# cannonLed.net
KiCad netlist of a schematic drawn in Altium Designer
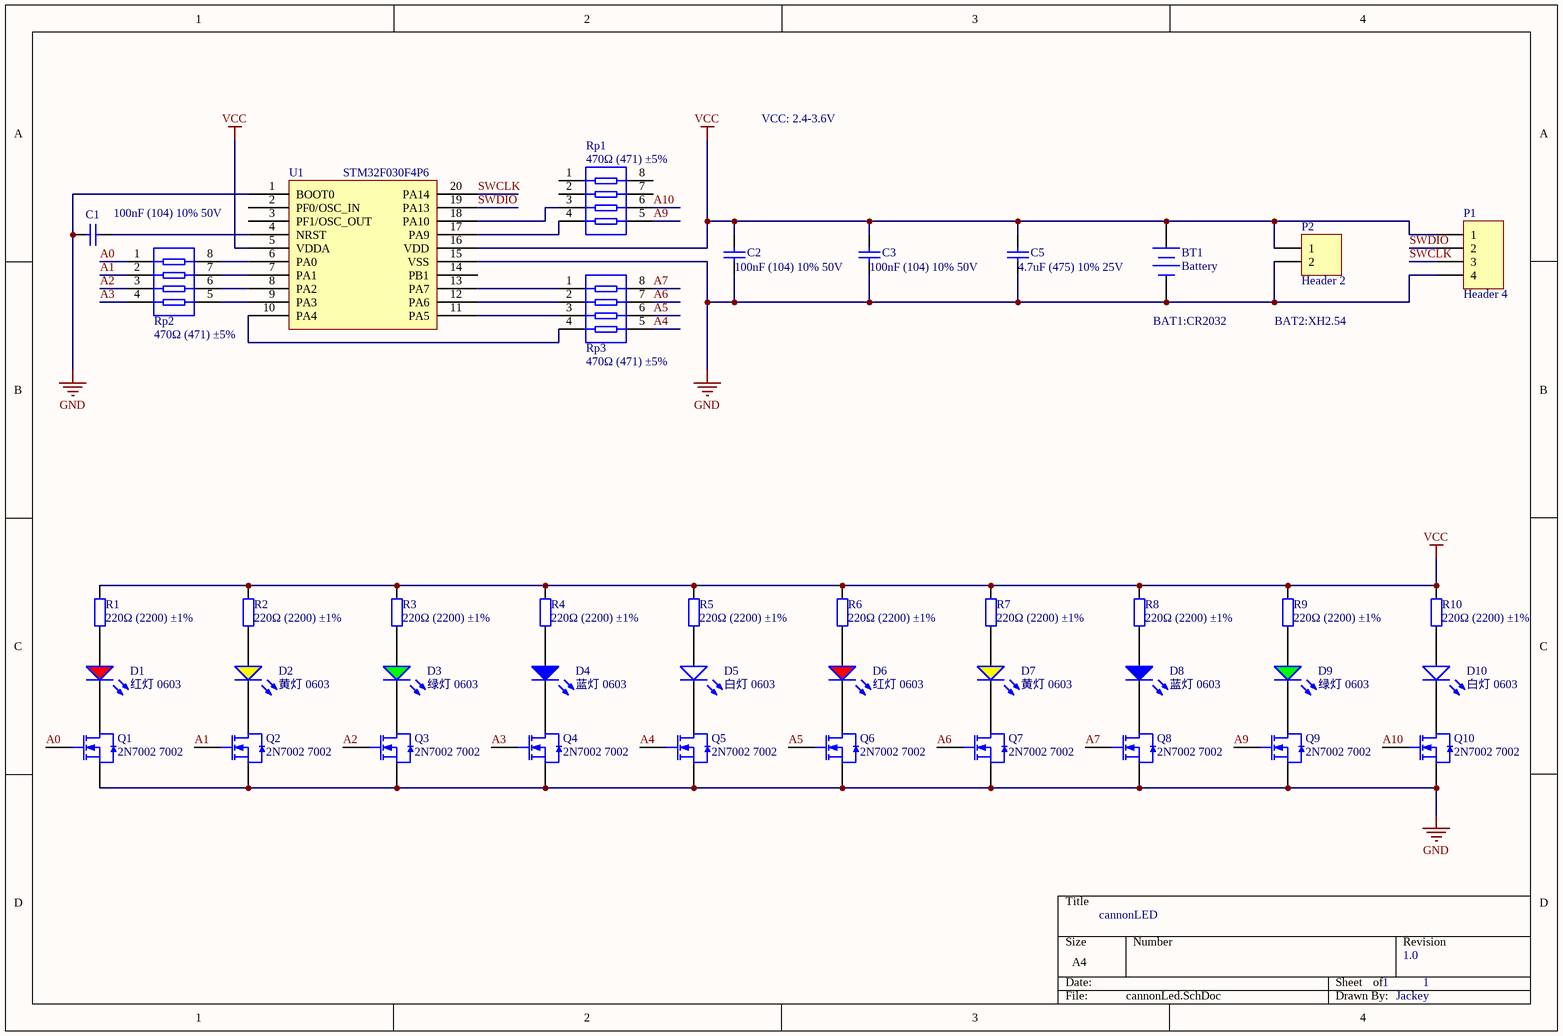
[diagram p0: cannonLed.SchDoc]

(export (version "E")
  (design (tool "Eeschema 10.0.6"))
  (components
    (comp (ref "BT1")
      (value "Battery")
      (footprint "CR2032")
      (description "Multicell Battery")
      (fields (field (name "PUBLISHER") "Altium Limited"))
      (libsource (lib "Miscellaneous Devices") (part "Battery"))
    )
    (comp (ref "C1")
      (value "100nF (104) 10% 50V")
      (footprint "0603_C")
      (description "贴片电容")
      (libsource (lib "Cap") (part "0603 100nF (104) 10% 50V"))
    )
    (comp (ref "C2")
      (value "100nF (104) 10% 50V")
      (footprint "0603_C")
      (description "贴片电容")
      (libsource (lib "Cap") (part "0603 100nF (104) 10% 50V"))
    )
    (comp (ref "C3")
      (value "100nF (104) 10% 50V")
      (footprint "0603_C")
      (description "贴片电容")
      (libsource (lib "Cap") (part "0603 100nF (104) 10% 50V"))
    )
    (comp (ref "C5")
      (value "4.7uF (475) 10% 25V")
      (footprint "0805_C")
      (description "贴片电容")
      (libsource (lib "Cap") (part "0805 4.7uF (475) 10% 25V"))
    )
    (comp (ref "D1")
      (value "红灯 0603")
      (footprint "0603_LED_S1")
      (description "发光二极管")
      (libsource (lib "LED") (part "0603 红灯"))
    )
    (comp (ref "D2")
      (value "黄灯 0603")
      (footprint "0603_LED_S1")
      (description "发光二极管")
      (libsource (lib "LED") (part "0603 黄灯"))
    )
    (comp (ref "D3")
      (value "绿灯 0603")
      (footprint "0603_LED_S1")
      (description "发光二极管")
      (libsource (lib "LED") (part "0603 绿灯"))
    )
    (comp (ref "D4")
      (value "蓝灯 0603")
      (footprint "0603_LED_S1")
      (description "发光二极管")
      (libsource (lib "LED") (part "0603 蓝灯"))
    )
    (comp (ref "D5")
      (value "白灯 0603")
      (footprint "0603_LED_S1")
      (description "发光二极管")
      (libsource (lib "LED") (part "0603 白灯"))
    )
    (comp (ref "D6")
      (value "红灯 0603")
      (footprint "0603_LED_S1")
      (description "发光二极管")
      (libsource (lib "LED") (part "0603 红灯"))
    )
    (comp (ref "D7")
      (value "黄灯 0603")
      (footprint "0603_LED_S1")
      (description "发光二极管")
      (libsource (lib "LED") (part "0603 黄灯"))
    )
    (comp (ref "D8")
      (value "蓝灯 0603")
      (footprint "0603_LED_S1")
      (description "发光二极管")
      (libsource (lib "LED") (part "0603 蓝灯"))
    )
    (comp (ref "D9")
      (value "绿灯 0603")
      (footprint "0603_LED_S1")
      (description "发光二极管")
      (libsource (lib "LED") (part "0603 绿灯"))
    )
    (comp (ref "D10")
      (value "白灯 0603")
      (footprint "0603_LED_S1")
      (description "发光二极管")
      (libsource (lib "LED") (part "0603 白灯"))
    )
    (comp (ref "P1")
      (value "Header 4")
      (footprint "HDR1X4")
      (description "Header, 4-Pin")
      (fields (field (name "PUBLISHER") "Altium Limited"))
      (libsource (lib "Miscellaneous Connectors") (part "Header 4"))
    )
    (comp (ref "P2")
      (value "Header 2")
      (footprint "HDR1X2")
      (description "Header, 2-Pin")
      (fields (field (name "PUBLISHER") "Altium Limited"))
      (libsource (lib "Miscellaneous Connectors") (part "Header 2"))
    )
    (comp (ref "Q1")
      (value "2N7002 7002")
      (footprint "SOT-23(SOT-23-3)")
      (description "MOS(场效应管)")
      (libsource (lib "MOS") (part "2N7002 7002"))
    )
    (comp (ref "Q2")
      (value "2N7002 7002")
      (footprint "SOT-23(SOT-23-3)")
      (description "MOS(场效应管)")
      (libsource (lib "MOS") (part "2N7002 7002"))
    )
    (comp (ref "Q3")
      (value "2N7002 7002")
      (footprint "SOT-23(SOT-23-3)")
      (description "MOS(场效应管)")
      (libsource (lib "MOS") (part "2N7002 7002"))
    )
    (comp (ref "Q4")
      (value "2N7002 7002")
      (footprint "SOT-23(SOT-23-3)")
      (description "MOS(场效应管)")
      (libsource (lib "MOS") (part "2N7002 7002"))
    )
    (comp (ref "Q5")
      (value "2N7002 7002")
      (footprint "SOT-23(SOT-23-3)")
      (description "MOS(场效应管)")
      (libsource (lib "MOS") (part "2N7002 7002"))
    )
    (comp (ref "Q6")
      (value "2N7002 7002")
      (footprint "SOT-23(SOT-23-3)")
      (description "MOS(场效应管)")
      (libsource (lib "MOS") (part "2N7002 7002"))
    )
    (comp (ref "Q7")
      (value "2N7002 7002")
      (footprint "SOT-23(SOT-23-3)")
      (description "MOS(场效应管)")
      (libsource (lib "MOS") (part "2N7002 7002"))
    )
    (comp (ref "Q8")
      (value "2N7002 7002")
      (footprint "SOT-23(SOT-23-3)")
      (description "MOS(场效应管)")
      (libsource (lib "MOS") (part "2N7002 7002"))
    )
    (comp (ref "Q9")
      (value "2N7002 7002")
      (footprint "SOT-23(SOT-23-3)")
      (description "MOS(场效应管)")
      (libsource (lib "MOS") (part "2N7002 7002"))
    )
    (comp (ref "Q10")
      (value "2N7002 7002")
      (footprint "SOT-23(SOT-23-3)")
      (description "MOS(场效应管)")
      (libsource (lib "MOS") (part "2N7002 7002"))
    )
    (comp (ref "R1")
      (value "220Ω (2200) ±1%")
      (footprint "0603_R")
      (description "贴片电阻")
      (libsource (lib "RES") (part "0603 220Ω (2200) 1%"))
    )
    (comp (ref "R2")
      (value "220Ω (2200) ±1%")
      (footprint "0603_R")
      (description "贴片电阻")
      (libsource (lib "") (part "0603 220Ω (2200) 1%_1"))
    )
    (comp (ref "R3")
      (value "220Ω (2200) ±1%")
      (footprint "0603_R")
      (description "贴片电阻")
      (libsource (lib "") (part "0603 220Ω (2200) 1%_1"))
    )
    (comp (ref "R4")
      (value "220Ω (2200) ±1%")
      (footprint "0603_R")
      (description "贴片电阻")
      (libsource (lib "") (part "0603 220Ω (2200) 1%_1"))
    )
    (comp (ref "R5")
      (value "220Ω (2200) ±1%")
      (footprint "0603_R")
      (description "贴片电阻")
      (libsource (lib "") (part "0603 220Ω (2200) 1%_1"))
    )
    (comp (ref "R6")
      (value "220Ω (2200) ±1%")
      (footprint "0603_R")
      (description "贴片电阻")
      (libsource (lib "") (part "0603 220Ω (2200) 1%_1"))
    )
    (comp (ref "R7")
      (value "220Ω (2200) ±1%")
      (footprint "0603_R")
      (description "贴片电阻")
      (libsource (lib "") (part "0603 220Ω (2200) 1%_1"))
    )
    (comp (ref "R8")
      (value "220Ω (2200) ±1%")
      (footprint "0603_R")
      (description "贴片电阻")
      (libsource (lib "") (part "0603 220Ω (2200) 1%_1"))
    )
    (comp (ref "R9")
      (value "220Ω (2200) ±1%")
      (footprint "0603_R")
      (description "贴片电阻")
      (libsource (lib "") (part "0603 220Ω (2200) 1%_1"))
    )
    (comp (ref "R10")
      (value "220Ω (2200) ±1%")
      (footprint "0603_R")
      (description "贴片电阻")
      (libsource (lib "") (part "0603 220Ω (2200) 1%_1"))
    )
    (comp (ref "Rp1")
      (value "470Ω (471) ±5%")
      (footprint "0603_Rx4")
      (description "贴片排阻")
      (libsource (lib "RES") (part "0603*4 470Ω (471) 5%"))
    )
    (comp (ref "Rp2")
      (value "470Ω (471) ±5%")
      (footprint "0603_Rx4")
      (description "贴片排阻")
      (libsource (lib "RES") (part "0603*4 470Ω (471) 5%"))
    )
    (comp (ref "Rp3")
      (value "470Ω (471) ±5%")
      (footprint "0603_Rx4")
      (description "贴片排阻")
      (libsource (lib "RES") (part "0603*4 470Ω (471) 5%"))
    )
    (comp (ref "U1")
      (value "STM32F030F4P6")
      (footprint "TSSOP-20")
      (description "ARM")
      (libsource (lib "MCU") (part "STM32F030F4P6"))
    )
  )
  (nets
    (net (code "1") (name "/A0") (class "Default")
      (node (ref "Q1") (pin "1") (pinfunction "G_1") (pintype "passive"))
      (node (ref "Rp2") (pin "1") (pinfunction "1_1") (pintype "passive"))
    )
    (net (code "2") (name "/A1") (class "Default")
      (node (ref "Q2") (pin "1") (pinfunction "G_1") (pintype "passive"))
      (node (ref "Rp2") (pin "2") (pinfunction "2_2") (pintype "passive"))
    )
    (net (code "3") (name "/A2") (class "Default")
      (node (ref "Q3") (pin "1") (pinfunction "G_1") (pintype "passive"))
      (node (ref "Rp2") (pin "3") (pinfunction "3_3") (pintype "passive"))
    )
    (net (code "4") (name "/A3") (class "Default")
      (node (ref "Q4") (pin "1") (pinfunction "G_1") (pintype "passive"))
      (node (ref "Rp2") (pin "4") (pinfunction "4_4") (pintype "passive"))
    )
    (net (code "5") (name "/A4") (class "Default")
      (node (ref "Q5") (pin "1") (pinfunction "G_1") (pintype "passive"))
      (node (ref "Rp3") (pin "5") (pinfunction "5_5") (pintype "passive"))
    )
    (net (code "6") (name "/A5") (class "Default")
      (node (ref "Q6") (pin "1") (pinfunction "G_1") (pintype "passive"))
      (node (ref "Rp3") (pin "6") (pinfunction "6_6") (pintype "passive"))
    )
    (net (code "7") (name "/A6") (class "Default")
      (node (ref "Q7") (pin "1") (pinfunction "G_1") (pintype "passive"))
      (node (ref "Rp3") (pin "7") (pinfunction "7_7") (pintype "passive"))
    )
    (net (code "8") (name "/A7") (class "Default")
      (node (ref "Q8") (pin "1") (pinfunction "G_1") (pintype "passive"))
      (node (ref "Rp3") (pin "8") (pinfunction "8_8") (pintype "passive"))
    )
    (net (code "9") (name "/A9") (class "Default")
      (node (ref "Q9") (pin "1") (pinfunction "G_1") (pintype "passive"))
      (node (ref "Rp1") (pin "5") (pinfunction "5_5") (pintype "passive"))
    )
    (net (code "10") (name "/A10") (class "Default")
      (node (ref "Q10") (pin "1") (pinfunction "G_1") (pintype "passive"))
      (node (ref "Rp1") (pin "6") (pinfunction "6_6") (pintype "passive"))
    )
    (net (code "11") (name "/SWCLK") (class "Default")
      (node (ref "P1") (pin "3") (pinfunction "3_3") (pintype "passive"))
      (node (ref "U1") (pin "20") (pinfunction "PA14_20") (pintype "passive"))
    )
    (net (code "12") (name "/SWDIO") (class "Default")
      (node (ref "P1") (pin "2") (pinfunction "2_2") (pintype "passive"))
      (node (ref "U1") (pin "19") (pinfunction "PA13_19") (pintype "passive"))
    )
    (net (code "13") (name "GND") (class "Default")
      (node (ref "BT1") (pin "2") (pinfunction "-_2") (pintype "passive"))
      (node (ref "C1") (pin "1") (pinfunction "1_1") (pintype "passive"))
      (node (ref "C2") (pin "1") (pinfunction "1_1") (pintype "passive"))
      (node (ref "C3") (pin "1") (pinfunction "1_1") (pintype "passive"))
      (node (ref "C5") (pin "1") (pinfunction "1_1") (pintype "passive"))
      (node (ref "P1") (pin "4") (pinfunction "4_4") (pintype "passive"))
      (node (ref "P2") (pin "2") (pinfunction "2_2") (pintype "passive"))
      (node (ref "Q1") (pin "2") (pinfunction "S_2") (pintype "passive"))
      (node (ref "Q10") (pin "2") (pinfunction "S_2") (pintype "passive"))
      (node (ref "Q2") (pin "2") (pinfunction "S_2") (pintype "passive"))
      (node (ref "Q3") (pin "2") (pinfunction "S_2") (pintype "passive"))
      (node (ref "Q4") (pin "2") (pinfunction "S_2") (pintype "passive"))
      (node (ref "Q5") (pin "2") (pinfunction "S_2") (pintype "passive"))
      (node (ref "Q6") (pin "2") (pinfunction "S_2") (pintype "passive"))
      (node (ref "Q7") (pin "2") (pinfunction "S_2") (pintype "passive"))
      (node (ref "Q8") (pin "2") (pinfunction "S_2") (pintype "passive"))
      (node (ref "Q9") (pin "2") (pinfunction "S_2") (pintype "passive"))
      (node (ref "U1") (pin "1") (pinfunction "BOOT0_1") (pintype "passive"))
      (node (ref "U1") (pin "15") (pinfunction "VSS_15") (pintype "passive"))
    )
    (net (code "14") (name "Net-(D1-PadA)") (class "Default")
      (node (ref "D1") (pin "A") (pinfunction "A_A") (pintype "passive"))
      (node (ref "R1") (pin "1") (pinfunction "1_1") (pintype "passive"))
    )
    (net (code "15") (name "Net-(D2-PadA)") (class "Default")
      (node (ref "D2") (pin "A") (pinfunction "A_A") (pintype "passive"))
      (node (ref "R2") (pin "2") (pinfunction "2_2") (pintype "passive"))
    )
    (net (code "16") (name "Net-(D3-PadA)") (class "Default")
      (node (ref "D3") (pin "A") (pinfunction "A_A") (pintype "passive"))
      (node (ref "R3") (pin "2") (pinfunction "2_2") (pintype "passive"))
    )
    (net (code "17") (name "Net-(D4-PadA)") (class "Default")
      (node (ref "D4") (pin "A") (pinfunction "A_A") (pintype "passive"))
      (node (ref "R4") (pin "2") (pinfunction "2_2") (pintype "passive"))
    )
    (net (code "18") (name "Net-(D5-PadA)") (class "Default")
      (node (ref "D5") (pin "A") (pinfunction "A_A") (pintype "passive"))
      (node (ref "R5") (pin "2") (pinfunction "2_2") (pintype "passive"))
    )
    (net (code "19") (name "Net-(D6-PadA)") (class "Default")
      (node (ref "D6") (pin "A") (pinfunction "A_A") (pintype "passive"))
      (node (ref "R6") (pin "2") (pinfunction "2_2") (pintype "passive"))
    )
    (net (code "20") (name "Net-(D7-PadA)") (class "Default")
      (node (ref "D7") (pin "A") (pinfunction "A_A") (pintype "passive"))
      (node (ref "R7") (pin "2") (pinfunction "2_2") (pintype "passive"))
    )
    (net (code "21") (name "Net-(D8-PadA)") (class "Default")
      (node (ref "D8") (pin "A") (pinfunction "A_A") (pintype "passive"))
      (node (ref "R8") (pin "2") (pinfunction "2_2") (pintype "passive"))
    )
    (net (code "22") (name "Net-(D9-PadA)") (class "Default")
      (node (ref "D9") (pin "A") (pinfunction "A_A") (pintype "passive"))
      (node (ref "R9") (pin "2") (pinfunction "2_2") (pintype "passive"))
    )
    (net (code "23") (name "Net-(D10-PadA)") (class "Default")
      (node (ref "D10") (pin "A") (pinfunction "A_A") (pintype "passive"))
      (node (ref "R10") (pin "2") (pinfunction "2_2") (pintype "passive"))
    )
    (net (code "24") (name "Net-(Q1-D)") (class "Default")
      (node (ref "D1") (pin "K") (pinfunction "K_K") (pintype "passive"))
      (node (ref "Q1") (pin "3") (pinfunction "D_3") (pintype "passive"))
    )
    (net (code "25") (name "Net-(Q2-D)") (class "Default")
      (node (ref "D2") (pin "K") (pinfunction "K_K") (pintype "passive"))
      (node (ref "Q2") (pin "3") (pinfunction "D_3") (pintype "passive"))
    )
    (net (code "26") (name "Net-(Q3-D)") (class "Default")
      (node (ref "D3") (pin "K") (pinfunction "K_K") (pintype "passive"))
      (node (ref "Q3") (pin "3") (pinfunction "D_3") (pintype "passive"))
    )
    (net (code "27") (name "Net-(Q4-D)") (class "Default")
      (node (ref "D4") (pin "K") (pinfunction "K_K") (pintype "passive"))
      (node (ref "Q4") (pin "3") (pinfunction "D_3") (pintype "passive"))
    )
    (net (code "28") (name "Net-(Q5-D)") (class "Default")
      (node (ref "D5") (pin "K") (pinfunction "K_K") (pintype "passive"))
      (node (ref "Q5") (pin "3") (pinfunction "D_3") (pintype "passive"))
    )
    (net (code "29") (name "Net-(Q6-D)") (class "Default")
      (node (ref "D6") (pin "K") (pinfunction "K_K") (pintype "passive"))
      (node (ref "Q6") (pin "3") (pinfunction "D_3") (pintype "passive"))
    )
    (net (code "30") (name "Net-(Q7-D)") (class "Default")
      (node (ref "D7") (pin "K") (pinfunction "K_K") (pintype "passive"))
      (node (ref "Q7") (pin "3") (pinfunction "D_3") (pintype "passive"))
    )
    (net (code "31") (name "Net-(Q8-D)") (class "Default")
      (node (ref "D8") (pin "K") (pinfunction "K_K") (pintype "passive"))
      (node (ref "Q8") (pin "3") (pinfunction "D_3") (pintype "passive"))
    )
    (net (code "32") (name "Net-(Q9-D)") (class "Default")
      (node (ref "D9") (pin "K") (pinfunction "K_K") (pintype "passive"))
      (node (ref "Q9") (pin "3") (pinfunction "D_3") (pintype "passive"))
    )
    (net (code "33") (name "Net-(Q10-D)") (class "Default")
      (node (ref "D10") (pin "K") (pinfunction "K_K") (pintype "passive"))
      (node (ref "Q10") (pin "3") (pinfunction "D_3") (pintype "passive"))
    )
    (net (code "34") (name "Net-(U1-NRST)") (class "Default")
      (node (ref "C1") (pin "2") (pinfunction "2_2") (pintype "passive"))
      (node (ref "U1") (pin "4") (pinfunction "NRST_4") (pintype "passive"))
    )
    (net (code "35") (name "Net-(U1-PA0)") (class "Default")
      (node (ref "Rp2") (pin "8") (pinfunction "8_8") (pintype "passive"))
      (node (ref "U1") (pin "6") (pinfunction "PA0_6") (pintype "passive"))
    )
    (net (code "36") (name "Net-(U1-PA1)") (class "Default")
      (node (ref "Rp2") (pin "7") (pinfunction "7_7") (pintype "passive"))
      (node (ref "U1") (pin "7") (pinfunction "PA1_7") (pintype "passive"))
    )
    (net (code "37") (name "Net-(U1-PA2)") (class "Default")
      (node (ref "Rp2") (pin "6") (pinfunction "6_6") (pintype "passive"))
      (node (ref "U1") (pin "8") (pinfunction "PA2_8") (pintype "passive"))
    )
    (net (code "38") (name "Net-(U1-PA3)") (class "Default")
      (node (ref "Rp2") (pin "5") (pinfunction "5_5") (pintype "passive"))
      (node (ref "U1") (pin "9") (pinfunction "PA3_9") (pintype "passive"))
    )
    (net (code "39") (name "Net-(U1-PA4)") (class "Default")
      (node (ref "Rp3") (pin "4") (pinfunction "4_4") (pintype "passive"))
      (node (ref "U1") (pin "10") (pinfunction "PA4_10") (pintype "passive"))
    )
    (net (code "40") (name "Net-(U1-PA5)") (class "Default")
      (node (ref "Rp3") (pin "3") (pinfunction "3_3") (pintype "passive"))
      (node (ref "U1") (pin "11") (pinfunction "PA5_11") (pintype "passive"))
    )
    (net (code "41") (name "Net-(U1-PA6)") (class "Default")
      (node (ref "Rp3") (pin "2") (pinfunction "2_2") (pintype "passive"))
      (node (ref "U1") (pin "12") (pinfunction "PA6_12") (pintype "passive"))
    )
    (net (code "42") (name "Net-(U1-PA7)") (class "Default")
      (node (ref "Rp3") (pin "1") (pinfunction "1_1") (pintype "passive"))
      (node (ref "U1") (pin "13") (pinfunction "PA7_13") (pintype "passive"))
    )
    (net (code "43") (name "Net-(U1-PA9)") (class "Default")
      (node (ref "Rp1") (pin "4") (pinfunction "4_4") (pintype "passive"))
      (node (ref "U1") (pin "17") (pinfunction "PA9_17") (pintype "passive"))
    )
    (net (code "44") (name "Net-(U1-PA10)") (class "Default")
      (node (ref "Rp1") (pin "3") (pinfunction "3_3") (pintype "passive"))
      (node (ref "U1") (pin "18") (pinfunction "PA10_18") (pintype "passive"))
    )
    (net (code "45") (name "VCC") (class "Default")
      (node (ref "BT1") (pin "1") (pinfunction "+_1") (pintype "passive"))
      (node (ref "C2") (pin "2") (pinfunction "2_2") (pintype "passive"))
      (node (ref "C3") (pin "2") (pinfunction "2_2") (pintype "passive"))
      (node (ref "C5") (pin "2") (pinfunction "2_2") (pintype "passive"))
      (node (ref "P1") (pin "1") (pinfunction "1_1") (pintype "passive"))
      (node (ref "P2") (pin "1") (pinfunction "1_1") (pintype "passive"))
      (node (ref "R1") (pin "2") (pinfunction "2_2") (pintype "passive"))
      (node (ref "R10") (pin "1") (pinfunction "1_1") (pintype "passive"))
      (node (ref "R2") (pin "1") (pinfunction "1_1") (pintype "passive"))
      (node (ref "R3") (pin "1") (pinfunction "1_1") (pintype "passive"))
      (node (ref "R4") (pin "1") (pinfunction "1_1") (pintype "passive"))
      (node (ref "R5") (pin "1") (pinfunction "1_1") (pintype "passive"))
      (node (ref "R6") (pin "1") (pinfunction "1_1") (pintype "passive"))
      (node (ref "R7") (pin "1") (pinfunction "1_1") (pintype "passive"))
      (node (ref "R8") (pin "1") (pinfunction "1_1") (pintype "passive"))
      (node (ref "R9") (pin "1") (pinfunction "1_1") (pintype "passive"))
      (node (ref "U1") (pin "16") (pinfunction "VDD_16") (pintype "passive"))
      (node (ref "U1") (pin "5") (pinfunction "VDDA_5") (pintype "passive"))
    )
    (net (code "46") (name "unconnected-(Rp1-Pad1)") (class "Default")
      (node (ref "Rp1") (pin "1") (pinfunction "1_1") (pintype "passive"))
    )
    (net (code "47") (name "unconnected-(Rp1-Pad2)") (class "Default")
      (node (ref "Rp1") (pin "2") (pinfunction "2_2") (pintype "passive"))
    )
    (net (code "48") (name "unconnected-(Rp1-Pad7)") (class "Default")
      (node (ref "Rp1") (pin "7") (pinfunction "7_7") (pintype "passive"))
    )
    (net (code "49") (name "unconnected-(Rp1-Pad8)") (class "Default")
      (node (ref "Rp1") (pin "8") (pinfunction "8_8") (pintype "passive"))
    )
    (net (code "50") (name "unconnected-(U1-PB1-Pad14)") (class "Default")
      (node (ref "U1") (pin "14") (pinfunction "PB1_14") (pintype "passive"))
    )
    (net (code "51") (name "unconnected-(U1-PF0{slash}OSC_IN-Pad2)") (class "Default")
      (node (ref "U1") (pin "2") (pinfunction "PF0/OSC_IN_2") (pintype "passive"))
    )
    (net (code "52") (name "unconnected-(U1-PF1{slash}OSC_OUT-Pad3)") (class "Default")
      (node (ref "U1") (pin "3") (pinfunction "PF1/OSC_OUT_3") (pintype "passive"))
    )
  )
)
